# design.net
KiCad netlist of a schematic drawn in Altium Designer
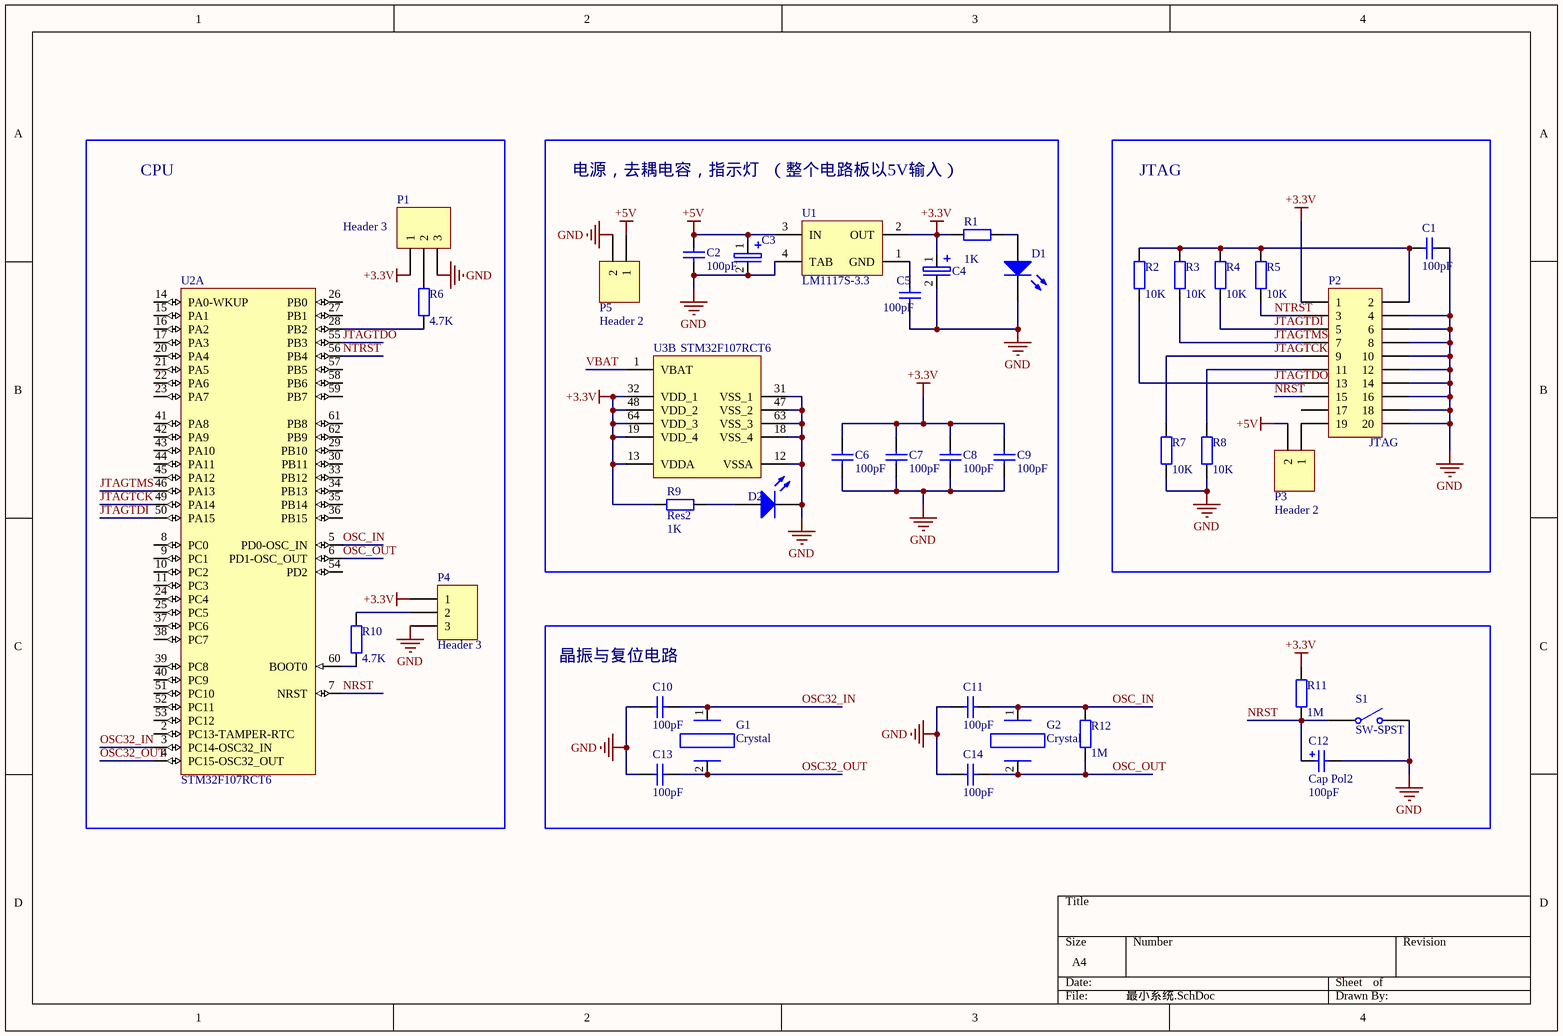
[diagram p0: 最小系统.SchDoc]

(export (version "E")
  (design (tool "Eeschema 10.0.6"))
  (components
    (comp (ref "C1")
      (value "100pF")
      (footprint "0805")
      (description "Ceramic Chip Capacitor - Standard")
      (fields (field (name "Comment") "C0805") (field (name "PUBLISHER") "Altium Limited"))
      (libsource (lib "KEMET Chip Capacitor") (part "C0805"))
    )
    (comp (ref "C2")
      (value "100pF")
      (footprint "0805")
      (description "Ceramic Chip Capacitor - Standard")
      (fields (field (name "Comment") "C0805") (field (name "PUBLISHER") "Altium Limited"))
      (libsource (lib "KEMET Chip Capacitor") (part "C0805"))
    )
    (comp (ref "C3") (value "Cap_tan") (footprint "CAP_tan") (libsource (lib "18221197") (part "Cap_tan")))
    (comp (ref "C4") (value "Cap_tan") (footprint "CAP_tan") (libsource (lib "18221197") (part "Cap_tan")))
    (comp (ref "C5")
      (value "100pF")
      (footprint "0805")
      (description "Ceramic Chip Capacitor - Standard")
      (fields (field (name "Comment") "C0805") (field (name "PUBLISHER") "Altium Limited"))
      (libsource (lib "KEMET Chip Capacitor") (part "C0805"))
    )
    (comp (ref "C6")
      (value "100pF")
      (footprint "0805")
      (description "Ceramic Chip Capacitor - Standard")
      (fields (field (name "Comment") "C0805") (field (name "PUBLISHER") "Altium Limited"))
      (libsource (lib "KEMET Chip Capacitor") (part "C0805"))
    )
    (comp (ref "C7")
      (value "100pF")
      (footprint "0805")
      (description "Ceramic Chip Capacitor - Standard")
      (fields (field (name "Comment") "C0805") (field (name "PUBLISHER") "Altium Limited"))
      (libsource (lib "KEMET Chip Capacitor") (part "C0805"))
    )
    (comp (ref "C8")
      (value "100pF")
      (footprint "0805")
      (description "Ceramic Chip Capacitor - Standard")
      (fields (field (name "Comment") "C0805") (field (name "PUBLISHER") "Altium Limited"))
      (libsource (lib "KEMET Chip Capacitor") (part "C0805"))
    )
    (comp (ref "C9")
      (value "100pF")
      (footprint "0805")
      (description "Ceramic Chip Capacitor - Standard")
      (fields (field (name "Comment") "C0805") (field (name "PUBLISHER") "Altium Limited"))
      (libsource (lib "KEMET Chip Capacitor") (part "C0805"))
    )
    (comp (ref "C10")
      (value "100pF")
      (footprint "0805")
      (description "Ceramic Chip Capacitor - Standard")
      (fields (field (name "Comment") "C0805") (field (name "PUBLISHER") "Altium Limited"))
      (libsource (lib "KEMET Chip Capacitor") (part "C0805"))
    )
    (comp (ref "C11")
      (value "100pF")
      (footprint "0805")
      (description "Ceramic Chip Capacitor - Standard")
      (fields (field (name "Comment") "C0805") (field (name "PUBLISHER") "Altium Limited"))
      (libsource (lib "KEMET Chip Capacitor") (part "C0805"))
    )
    (comp (ref "C12")
      (value "Cap Pol2")
      (footprint "POLAR0.8")
      (description "Polarized Capacitor (Axial)")
      (fields (field (name "ALTIUM_VALUE") "100pF") (field (name "PUBLISHER") "Altium Limited"))
      (libsource (lib "Miscellaneous Devices") (part "Cap Pol2"))
    )
    (comp (ref "C13")
      (value "100pF")
      (footprint "0805")
      (description "Ceramic Chip Capacitor - Standard")
      (fields (field (name "Comment") "C0805") (field (name "PUBLISHER") "Altium Limited"))
      (libsource (lib "KEMET Chip Capacitor") (part "C0805"))
    )
    (comp (ref "C14")
      (value "100pF")
      (footprint "0805")
      (description "Ceramic Chip Capacitor - Standard")
      (fields (field (name "Comment") "C0805") (field (name "PUBLISHER") "Altium Limited"))
      (libsource (lib "KEMET Chip Capacitor") (part "C0805"))
    )
    (comp (ref "D1")
      (value "LED3")
      (footprint "3.5X2.8X1.9")
      (description "Typical BLUE SiC LED")
      (fields (field (name "PUBLISHER") "Altium Limited"))
      (libsource (lib "Miscellaneous Devices") (part "LED3"))
    )
    (comp (ref "D2")
      (value "LED3")
      (footprint "3.5X2.8X1.9")
      (description "Typical BLUE SiC LED")
      (fields (field (name "PUBLISHER") "Altium Limited"))
      (libsource (lib "Miscellaneous Devices") (part "LED3"))
    )
    (comp (ref "G1") (value "Crystal") (footprint "Crystal") (libsource (lib "18221197") (part "Crystal")))
    (comp (ref "G2") (value "Crystal") (footprint "Crystal") (libsource (lib "18221197") (part "Crystal")))
    (comp (ref "P1")
      (value "Header 3")
      (footprint "HDR1X3")
      (description "Header, 3-Pin")
      (fields (field (name "PUBLISHER") "Altium Limited"))
      (libsource (lib "") (part "Header 3_1"))
    )
    (comp (ref "P2")
      (value "JTAG")
      (footprint "HDR2X10")
      (description "Header, 10-Pin, Dual row")
      (fields (field (name "PUBLISHER") "Altium Limited"))
      (libsource (lib "Miscellaneous Connectors") (part "Header 10X2"))
    )
    (comp (ref "P3")
      (value "Header 2")
      (footprint "HDR1X2")
      (description "Header, 2-Pin")
      (fields (field (name "PUBLISHER") "Altium Limited"))
      (libsource (lib "Miscellaneous Connectors") (part "Header 2"))
    )
    (comp (ref "P4")
      (value "Header 3")
      (footprint "HDR1X3")
      (description "Header, 3-Pin")
      (fields (field (name "PUBLISHER") "Altium Limited"))
      (libsource (lib "Miscellaneous Connectors") (part "Header 3"))
    )
    (comp (ref "P5")
      (value "Header 2")
      (footprint "HDR1X2")
      (description "Header, 2-Pin")
      (fields (field (name "PUBLISHER") "Altium Limited"))
      (libsource (lib "Miscellaneous Connectors") (part "Header 2"))
    )
    (comp (ref "R1")
      (value "1K")
      (footprint "AXIAL-0.4")
      (description "Resistor")
      (fields (field (name "Comment") "Res2") (field (name "PUBLISHER") "Altium Limited"))
      (libsource (lib "") (part "Res2_1"))
    )
    (comp (ref "R2")
      (value "10K")
      (footprint "AXIAL-0.4")
      (description "Resistor")
      (fields (field (name "Comment") "Res2") (field (name "PUBLISHER") "Altium Limited"))
      (libsource (lib "Miscellaneous Devices") (part "Res2"))
    )
    (comp (ref "R3")
      (value "10K")
      (footprint "AXIAL-0.4")
      (description "Resistor")
      (fields (field (name "Comment") "Res2") (field (name "PUBLISHER") "Altium Limited"))
      (libsource (lib "Miscellaneous Devices") (part "Res2"))
    )
    (comp (ref "R4")
      (value "10K")
      (footprint "AXIAL-0.4")
      (description "Resistor")
      (fields (field (name "Comment") "Res2") (field (name "PUBLISHER") "Altium Limited"))
      (libsource (lib "Miscellaneous Devices") (part "Res2"))
    )
    (comp (ref "R5")
      (value "10K")
      (footprint "AXIAL-0.4")
      (description "Resistor")
      (fields (field (name "Comment") "Res2") (field (name "PUBLISHER") "Altium Limited"))
      (libsource (lib "Miscellaneous Devices") (part "Res2"))
    )
    (comp (ref "R6")
      (value "4.7K")
      (footprint "AXIAL-0.4")
      (description "Resistor")
      (fields (field (name "Comment") "Res2") (field (name "PUBLISHER") "Altium Limited"))
      (libsource (lib "Miscellaneous Devices") (part "Res2"))
    )
    (comp (ref "R7")
      (value "10K")
      (footprint "AXIAL-0.4")
      (description "Resistor")
      (fields (field (name "Comment") "Res2") (field (name "PUBLISHER") "Altium Limited"))
      (libsource (lib "Miscellaneous Devices") (part "Res2"))
    )
    (comp (ref "R8")
      (value "10K")
      (footprint "AXIAL-0.4")
      (description "Resistor")
      (fields (field (name "Comment") "Res2") (field (name "PUBLISHER") "Altium Limited"))
      (libsource (lib "Miscellaneous Devices") (part "Res2"))
    )
    (comp (ref "R9")
      (value "Res2")
      (footprint "AXIAL-0.4")
      (description "Resistor")
      (fields (field (name "ALTIUM_VALUE") "1K") (field (name "PUBLISHER") "Altium Limited"))
      (libsource (lib "") (part "Res2_1"))
    )
    (comp (ref "R10")
      (value "4.7K")
      (footprint "AXIAL-0.4")
      (description "Resistor")
      (fields (field (name "Comment") "Res2") (field (name "PUBLISHER") "Altium Limited"))
      (libsource (lib "Miscellaneous Devices") (part "Res2"))
    )
    (comp (ref "R11")
      (value "1M")
      (footprint "AXIAL-0.4")
      (description "Resistor")
      (fields (field (name "Comment") "Res2") (field (name "PUBLISHER") "Altium Limited"))
      (libsource (lib "Miscellaneous Devices") (part "Res2"))
    )
    (comp (ref "R12")
      (value "1M")
      (footprint "AXIAL-0.4")
      (description "Resistor")
      (fields (field (name "Comment") "Res2") (field (name "PUBLISHER") "Altium Limited"))
      (libsource (lib "Miscellaneous Devices") (part "Res2"))
    )
    (comp (ref "S1")
      (value "SW-SPST")
      (footprint "SPST-2")
      (description "Single-Pole, Single-Throw Switch")
      (fields (field (name "PUBLISHER") "Altium Limited"))
      (libsource (lib "Miscellaneous Devices") (part "SW-SPST"))
    )
    (comp (ref "U1")
      (value "LM1117S-3.3")
      (footprint "TS3B_N")
      (description "800mA Low-Dropout Linear Regulator, 3-pin TO-263")
      (fields
        (field (name "MANUFACTURER") "National Semiconductor")
        (field (name "PUBLISHER") "Altium Limited")
      )
      (libsource (lib "NSC Legacy") (part "LM1117S-3.3"))
    )
    (comp (ref "U2")
      (value "STM32F107RCT6")
      (footprint "STM-LQFP64_N")
      (libsource (lib "STMicroelectronics STM32 F1") (part "STM32F107RCT6"))
    )
    (comp (ref "U3")
      (value "STM32F107RCT6")
      (footprint "STM-LQFP64_M")
      (libsource (lib "Altium Content Vault") (part "MC-ARM-STM32F10X-SQ64"))
    )
  )
  (nets
    (net (code "1") (name "+3.3V") (class "Default")
      (node (ref "C4") (pin "1") (pinfunction "1_1") (pintype "passive"))
      (node (ref "C6") (pin "1") (pinfunction "1_1") (pintype "passive"))
      (node (ref "C7") (pin "1") (pinfunction "1_1") (pintype "passive"))
      (node (ref "C8") (pin "1") (pinfunction "1_1") (pintype "passive"))
      (node (ref "C9") (pin "1") (pinfunction "1_1") (pintype "passive"))
      (node (ref "P1") (pin "1") (pinfunction "1_1") (pintype "passive"))
      (node (ref "P2") (pin "1") (pinfunction "1_1") (pintype "passive"))
      (node (ref "P4") (pin "1") (pinfunction "1_1") (pintype "passive"))
      (node (ref "R1") (pin "1") (pinfunction "1_1") (pintype "passive"))
      (node (ref "R11") (pin "2") (pinfunction "2_2") (pintype "passive"))
      (node (ref "R9") (pin "1") (pinfunction "1_1") (pintype "passive"))
      (node (ref "U1") (pin "2") (pinfunction "OUT_2") (pintype "power_in"))
      (node (ref "U3") (pin "13") (pinfunction "VDDA_13") (pintype "power_in"))
      (node (ref "U3") (pin "19") (pinfunction "VDD_4_19") (pintype "power_in"))
      (node (ref "U3") (pin "32") (pinfunction "VDD_1_32") (pintype "power_in"))
      (node (ref "U3") (pin "48") (pinfunction "VDD_2_48") (pintype "power_in"))
      (node (ref "U3") (pin "64") (pinfunction "VDD_3_64") (pintype "power_in"))
    )
    (net (code "2") (name "+5V") (class "Default")
      (node (ref "C2") (pin "1") (pinfunction "1_1") (pintype "passive"))
      (node (ref "C3") (pin "1") (pinfunction "1_1") (pintype "passive"))
      (node (ref "P3") (pin "2") (pinfunction "2_2") (pintype "passive"))
      (node (ref "P5") (pin "1") (pinfunction "1_1") (pintype "passive"))
      (node (ref "U1") (pin "3") (pinfunction "IN_3") (pintype "power_in"))
    )
    (net (code "3") (name "/JTAGTCK") (class "Default")
      (node (ref "P2") (pin "9") (pinfunction "9_9") (pintype "passive"))
      (node (ref "R7") (pin "2") (pinfunction "2_2") (pintype "passive"))
      (node (ref "U2") (pin "49") (pinfunction "PA14_49") (pintype "bidirectional"))
    )
    (net (code "4") (name "/JTAGTDI") (class "Default")
      (node (ref "P2") (pin "5") (pinfunction "5_5") (pintype "passive"))
      (node (ref "R4") (pin "1") (pinfunction "1_1") (pintype "passive"))
      (node (ref "U2") (pin "50") (pinfunction "PA15_50") (pintype "bidirectional"))
    )
    (net (code "5") (name "/JTAGTDO") (class "Default")
      (node (ref "P2") (pin "13") (pinfunction "13_13") (pintype "passive"))
      (node (ref "R2") (pin "1") (pinfunction "1_1") (pintype "passive"))
      (node (ref "U2") (pin "55") (pinfunction "PB3_55") (pintype "bidirectional"))
    )
    (net (code "6") (name "/JTAGTMS") (class "Default")
      (node (ref "P2") (pin "7") (pinfunction "7_7") (pintype "passive"))
      (node (ref "R3") (pin "1") (pinfunction "1_1") (pintype "passive"))
      (node (ref "U2") (pin "46") (pinfunction "PA13_46") (pintype "bidirectional"))
    )
    (net (code "7") (name "/NRST") (class "Default")
      (node (ref "C12") (pin "1") (pinfunction "1_1") (pintype "passive"))
      (node (ref "P2") (pin "15") (pinfunction "15_15") (pintype "passive"))
      (node (ref "R11") (pin "1") (pinfunction "1_1") (pintype "passive"))
      (node (ref "S1") (pin "1") (pinfunction "COMMON_1") (pintype "passive"))
      (node (ref "U2") (pin "7") (pinfunction "NRST_7") (pintype "bidirectional"))
    )
    (net (code "8") (name "/NTRST") (class "Default")
      (node (ref "P2") (pin "3") (pinfunction "3_3") (pintype "passive"))
      (node (ref "R5") (pin "1") (pinfunction "1_1") (pintype "passive"))
      (node (ref "U2") (pin "56") (pinfunction "PB4_56") (pintype "bidirectional"))
    )
    (net (code "9") (name "/OSC32_IN") (class "Default")
      (node (ref "C10") (pin "2") (pinfunction "2_2") (pintype "passive"))
      (node (ref "G1") (pin "1") (pinfunction "1_1") (pintype "passive"))
      (node (ref "U2") (pin "3") (pinfunction "PC14-OSC32_IN_3") (pintype "bidirectional"))
    )
    (net (code "10") (name "/OSC32_OUT") (class "Default")
      (node (ref "C13") (pin "2") (pinfunction "2_2") (pintype "passive"))
      (node (ref "G1") (pin "2") (pinfunction "2_2") (pintype "passive"))
      (node (ref "U2") (pin "4") (pinfunction "PC15-OSC32_OUT_4") (pintype "bidirectional"))
    )
    (net (code "11") (name "/OSC_IN") (class "Default")
      (node (ref "C11") (pin "2") (pinfunction "2_2") (pintype "passive"))
      (node (ref "G2") (pin "1") (pinfunction "1_1") (pintype "passive"))
      (node (ref "R12") (pin "2") (pinfunction "2_2") (pintype "passive"))
      (node (ref "U2") (pin "5") (pinfunction "PD0-OSC_IN_5") (pintype "bidirectional"))
    )
    (net (code "12") (name "/OSC_OUT") (class "Default")
      (node (ref "C14") (pin "2") (pinfunction "2_2") (pintype "passive"))
      (node (ref "G2") (pin "2") (pinfunction "2_2") (pintype "passive"))
      (node (ref "R12") (pin "1") (pinfunction "1_1") (pintype "passive"))
      (node (ref "U2") (pin "6") (pinfunction "PD1-OSC_OUT_6") (pintype "bidirectional"))
    )
    (net (code "13") (name "/VBAT") (class "Default")
      (node (ref "U3") (pin "1") (pinfunction "VBAT_1") (pintype "power_in"))
    )
    (net (code "14") (name "GND") (class "Default")
      (node (ref "C1") (pin "2") (pinfunction "2_2") (pintype "passive"))
      (node (ref "C10") (pin "1") (pinfunction "1_1") (pintype "passive"))
      (node (ref "C11") (pin "1") (pinfunction "1_1") (pintype "passive"))
      (node (ref "C12") (pin "2") (pinfunction "2_2") (pintype "passive"))
      (node (ref "C13") (pin "1") (pinfunction "1_1") (pintype "passive"))
      (node (ref "C14") (pin "1") (pinfunction "1_1") (pintype "passive"))
      (node (ref "C2") (pin "2") (pinfunction "2_2") (pintype "passive"))
      (node (ref "C3") (pin "2") (pinfunction "2_2") (pintype "passive"))
      (node (ref "C4") (pin "2") (pinfunction "2_2") (pintype "passive"))
      (node (ref "C5") (pin "2") (pinfunction "2_2") (pintype "passive"))
      (node (ref "C6") (pin "2") (pinfunction "2_2") (pintype "passive"))
      (node (ref "C7") (pin "2") (pinfunction "2_2") (pintype "passive"))
      (node (ref "C8") (pin "2") (pinfunction "2_2") (pintype "passive"))
      (node (ref "C9") (pin "2") (pinfunction "2_2") (pintype "passive"))
      (node (ref "D1") (pin "2") (pinfunction "K_2") (pintype "passive"))
      (node (ref "D2") (pin "2") (pinfunction "K_2") (pintype "passive"))
      (node (ref "P1") (pin "3") (pinfunction "3_3") (pintype "passive"))
      (node (ref "P2") (pin "10") (pinfunction "10_10") (pintype "passive"))
      (node (ref "P2") (pin "12") (pinfunction "12_12") (pintype "passive"))
      (node (ref "P2") (pin "14") (pinfunction "14_14") (pintype "passive"))
      (node (ref "P2") (pin "16") (pinfunction "16_16") (pintype "passive"))
      (node (ref "P2") (pin "18") (pinfunction "18_18") (pintype "passive"))
      (node (ref "P2") (pin "20") (pinfunction "20_20") (pintype "passive"))
      (node (ref "P2") (pin "4") (pinfunction "4_4") (pintype "passive"))
      (node (ref "P2") (pin "6") (pinfunction "6_6") (pintype "passive"))
      (node (ref "P2") (pin "8") (pinfunction "8_8") (pintype "passive"))
      (node (ref "P4") (pin "3") (pinfunction "3_3") (pintype "passive"))
      (node (ref "P5") (pin "2") (pinfunction "2_2") (pintype "passive"))
      (node (ref "R7") (pin "1") (pinfunction "1_1") (pintype "passive"))
      (node (ref "R8") (pin "1") (pinfunction "1_1") (pintype "passive"))
      (node (ref "S1") (pin "2") (pinfunction "NO_2") (pintype "passive"))
      (node (ref "U1") (pin "4") (pinfunction "TAB_4") (pintype "power_in"))
      (node (ref "U3") (pin "12") (pinfunction "VSSA_12") (pintype "power_in"))
      (node (ref "U3") (pin "18") (pinfunction "VSS_4_18") (pintype "power_in"))
      (node (ref "U3") (pin "31") (pinfunction "VSS_1_31") (pintype "power_in"))
      (node (ref "U3") (pin "47") (pinfunction "VSS_2_47") (pintype "power_in"))
      (node (ref "U3") (pin "63") (pinfunction "VSS_3_63") (pintype "power_in"))
    )
    (net (code "15") (name "Net-(C1-Pad1)") (class "Default")
      (node (ref "C1") (pin "1") (pinfunction "1_1") (pintype "passive"))
      (node (ref "P2") (pin "2") (pinfunction "2_2") (pintype "passive"))
      (node (ref "R2") (pin "2") (pinfunction "2_2") (pintype "passive"))
      (node (ref "R3") (pin "2") (pinfunction "2_2") (pintype "passive"))
      (node (ref "R4") (pin "2") (pinfunction "2_2") (pintype "passive"))
      (node (ref "R5") (pin "2") (pinfunction "2_2") (pintype "passive"))
    )
    (net (code "16") (name "Net-(D1-A)") (class "Default")
      (node (ref "D1") (pin "1") (pinfunction "A_1") (pintype "passive"))
      (node (ref "R1") (pin "2") (pinfunction "2_2") (pintype "passive"))
    )
    (net (code "17") (name "Net-(D2-A)") (class "Default")
      (node (ref "D2") (pin "1") (pinfunction "A_1") (pintype "passive"))
      (node (ref "R9") (pin "2") (pinfunction "2_2") (pintype "passive"))
    )
    (net (code "18") (name "Net-(P1-Pad2)") (class "Default")
      (node (ref "P1") (pin "2") (pinfunction "2_2") (pintype "passive"))
      (node (ref "R6") (pin "2") (pinfunction "2_2") (pintype "passive"))
    )
    (net (code "19") (name "Net-(P2-Pad11)") (class "Default")
      (node (ref "P2") (pin "11") (pinfunction "11_11") (pintype "passive"))
      (node (ref "R8") (pin "2") (pinfunction "2_2") (pintype "passive"))
    )
    (net (code "20") (name "Net-(P2-Pad19)") (class "Default")
      (node (ref "P2") (pin "19") (pinfunction "19_19") (pintype "passive"))
      (node (ref "P3") (pin "1") (pinfunction "1_1") (pintype "passive"))
    )
    (net (code "21") (name "Net-(P4-Pad2)") (class "Default")
      (node (ref "P4") (pin "2") (pinfunction "2_2") (pintype "passive"))
      (node (ref "R10") (pin "2") (pinfunction "2_2") (pintype "passive"))
    )
    (net (code "22") (name "Net-(U1-GND)") (class "Default")
      (node (ref "C5") (pin "1") (pinfunction "1_1") (pintype "passive"))
      (node (ref "U1") (pin "1") (pinfunction "GND_1") (pintype "power_in"))
    )
    (net (code "23") (name "Net-(U2A-BOOT0)") (class "Default")
      (node (ref "R10") (pin "1") (pinfunction "1_1") (pintype "passive"))
      (node (ref "U2") (pin "60") (pinfunction "BOOT0_60") (pintype "input"))
    )
    (net (code "24") (name "Net-(U2A-PB2)") (class "Default")
      (node (ref "R6") (pin "1") (pinfunction "1_1") (pintype "passive"))
      (node (ref "U2") (pin "28") (pinfunction "PB2_28") (pintype "bidirectional"))
    )
    (net (code "25") (name "unconnected-(P2-Pad17)") (class "Default")
      (node (ref "P2") (pin "17") (pinfunction "17_17") (pintype "passive"))
    )
    (net (code "26") (name "unconnected-(U2A-PA0-WKUP-Pad14)") (class "Default")
      (node (ref "U2") (pin "14") (pinfunction "PA0-WKUP_14") (pintype "bidirectional"))
    )
    (net (code "27") (name "unconnected-(U2A-PA1-Pad15)") (class "Default")
      (node (ref "U2") (pin "15") (pinfunction "PA1_15") (pintype "bidirectional"))
    )
    (net (code "28") (name "unconnected-(U2A-PA2-Pad16)") (class "Default")
      (node (ref "U2") (pin "16") (pinfunction "PA2_16") (pintype "bidirectional"))
    )
    (net (code "29") (name "unconnected-(U2A-PA3-Pad17)") (class "Default")
      (node (ref "U2") (pin "17") (pinfunction "PA3_17") (pintype "bidirectional"))
    )
    (net (code "30") (name "unconnected-(U2A-PA4-Pad20)") (class "Default")
      (node (ref "U2") (pin "20") (pinfunction "PA4_20") (pintype "bidirectional"))
    )
    (net (code "31") (name "unconnected-(U2A-PA5-Pad21)") (class "Default")
      (node (ref "U2") (pin "21") (pinfunction "PA5_21") (pintype "bidirectional"))
    )
    (net (code "32") (name "unconnected-(U2A-PA6-Pad22)") (class "Default")
      (node (ref "U2") (pin "22") (pinfunction "PA6_22") (pintype "bidirectional"))
    )
    (net (code "33") (name "unconnected-(U2A-PA7-Pad23)") (class "Default")
      (node (ref "U2") (pin "23") (pinfunction "PA7_23") (pintype "bidirectional"))
    )
    (net (code "34") (name "unconnected-(U2A-PA8-Pad41)") (class "Default")
      (node (ref "U2") (pin "41") (pinfunction "PA8_41") (pintype "bidirectional"))
    )
    (net (code "35") (name "unconnected-(U2A-PA9-Pad42)") (class "Default")
      (node (ref "U2") (pin "42") (pinfunction "PA9_42") (pintype "bidirectional"))
    )
    (net (code "36") (name "unconnected-(U2A-PA10-Pad43)") (class "Default")
      (node (ref "U2") (pin "43") (pinfunction "PA10_43") (pintype "bidirectional"))
    )
    (net (code "37") (name "unconnected-(U2A-PA11-Pad44)") (class "Default")
      (node (ref "U2") (pin "44") (pinfunction "PA11_44") (pintype "bidirectional"))
    )
    (net (code "38") (name "unconnected-(U2A-PA12-Pad45)") (class "Default")
      (node (ref "U2") (pin "45") (pinfunction "PA12_45") (pintype "bidirectional"))
    )
    (net (code "39") (name "unconnected-(U2A-PB0-Pad26)") (class "Default")
      (node (ref "U2") (pin "26") (pinfunction "PB0_26") (pintype "bidirectional"))
    )
    (net (code "40") (name "unconnected-(U2A-PB1-Pad27)") (class "Default")
      (node (ref "U2") (pin "27") (pinfunction "PB1_27") (pintype "bidirectional"))
    )
    (net (code "41") (name "unconnected-(U2A-PB5-Pad57)") (class "Default")
      (node (ref "U2") (pin "57") (pinfunction "PB5_57") (pintype "bidirectional"))
    )
    (net (code "42") (name "unconnected-(U2A-PB6-Pad58)") (class "Default")
      (node (ref "U2") (pin "58") (pinfunction "PB6_58") (pintype "bidirectional"))
    )
    (net (code "43") (name "unconnected-(U2A-PB7-Pad59)") (class "Default")
      (node (ref "U2") (pin "59") (pinfunction "PB7_59") (pintype "bidirectional"))
    )
    (net (code "44") (name "unconnected-(U2A-PB8-Pad61)") (class "Default")
      (node (ref "U2") (pin "61") (pinfunction "PB8_61") (pintype "bidirectional"))
    )
    (net (code "45") (name "unconnected-(U2A-PB9-Pad62)") (class "Default")
      (node (ref "U2") (pin "62") (pinfunction "PB9_62") (pintype "bidirectional"))
    )
    (net (code "46") (name "unconnected-(U2A-PB10-Pad29)") (class "Default")
      (node (ref "U2") (pin "29") (pinfunction "PB10_29") (pintype "bidirectional"))
    )
    (net (code "47") (name "unconnected-(U2A-PB11-Pad30)") (class "Default")
      (node (ref "U2") (pin "30") (pinfunction "PB11_30") (pintype "bidirectional"))
    )
    (net (code "48") (name "unconnected-(U2A-PB12-Pad33)") (class "Default")
      (node (ref "U2") (pin "33") (pinfunction "PB12_33") (pintype "bidirectional"))
    )
    (net (code "49") (name "unconnected-(U2A-PB13-Pad34)") (class "Default")
      (node (ref "U2") (pin "34") (pinfunction "PB13_34") (pintype "bidirectional"))
    )
    (net (code "50") (name "unconnected-(U2A-PB14-Pad35)") (class "Default")
      (node (ref "U2") (pin "35") (pinfunction "PB14_35") (pintype "bidirectional"))
    )
    (net (code "51") (name "unconnected-(U2A-PB15-Pad36)") (class "Default")
      (node (ref "U2") (pin "36") (pinfunction "PB15_36") (pintype "bidirectional"))
    )
    (net (code "52") (name "unconnected-(U2A-PC0-Pad8)") (class "Default")
      (node (ref "U2") (pin "8") (pinfunction "PC0_8") (pintype "bidirectional"))
    )
    (net (code "53") (name "unconnected-(U2A-PC1-Pad9)") (class "Default")
      (node (ref "U2") (pin "9") (pinfunction "PC1_9") (pintype "bidirectional"))
    )
    (net (code "54") (name "unconnected-(U2A-PC2-Pad10)") (class "Default")
      (node (ref "U2") (pin "10") (pinfunction "PC2_10") (pintype "bidirectional"))
    )
    (net (code "55") (name "unconnected-(U2A-PC3-Pad11)") (class "Default")
      (node (ref "U2") (pin "11") (pinfunction "PC3_11") (pintype "bidirectional"))
    )
    (net (code "56") (name "unconnected-(U2A-PC4-Pad24)") (class "Default")
      (node (ref "U2") (pin "24") (pinfunction "PC4_24") (pintype "bidirectional"))
    )
    (net (code "57") (name "unconnected-(U2A-PC5-Pad25)") (class "Default")
      (node (ref "U2") (pin "25") (pinfunction "PC5_25") (pintype "bidirectional"))
    )
    (net (code "58") (name "unconnected-(U2A-PC6-Pad37)") (class "Default")
      (node (ref "U2") (pin "37") (pinfunction "PC6_37") (pintype "bidirectional"))
    )
    (net (code "59") (name "unconnected-(U2A-PC7-Pad38)") (class "Default")
      (node (ref "U2") (pin "38") (pinfunction "PC7_38") (pintype "bidirectional"))
    )
    (net (code "60") (name "unconnected-(U2A-PC8-Pad39)") (class "Default")
      (node (ref "U2") (pin "39") (pinfunction "PC8_39") (pintype "bidirectional"))
    )
    (net (code "61") (name "unconnected-(U2A-PC9-Pad40)") (class "Default")
      (node (ref "U2") (pin "40") (pinfunction "PC9_40") (pintype "bidirectional"))
    )
    (net (code "62") (name "unconnected-(U2A-PC10-Pad51)") (class "Default")
      (node (ref "U2") (pin "51") (pinfunction "PC10_51") (pintype "bidirectional"))
    )
    (net (code "63") (name "unconnected-(U2A-PC11-Pad52)") (class "Default")
      (node (ref "U2") (pin "52") (pinfunction "PC11_52") (pintype "bidirectional"))
    )
    (net (code "64") (name "unconnected-(U2A-PC12-Pad53)") (class "Default")
      (node (ref "U2") (pin "53") (pinfunction "PC12_53") (pintype "bidirectional"))
    )
    (net (code "65") (name "unconnected-(U2A-PC13-TAMPER-RTC-Pad2)") (class "Default")
      (node (ref "U2") (pin "2") (pinfunction "PC13-TAMPER-RTC_2") (pintype "bidirectional"))
    )
    (net (code "66") (name "unconnected-(U2A-PD2-Pad54)") (class "Default")
      (node (ref "U2") (pin "54") (pinfunction "PD2_54") (pintype "bidirectional"))
    )
  )
)
